# quantum-switch-control-panel.net
KiCad netlist of a schematic drawn in Altium Designer
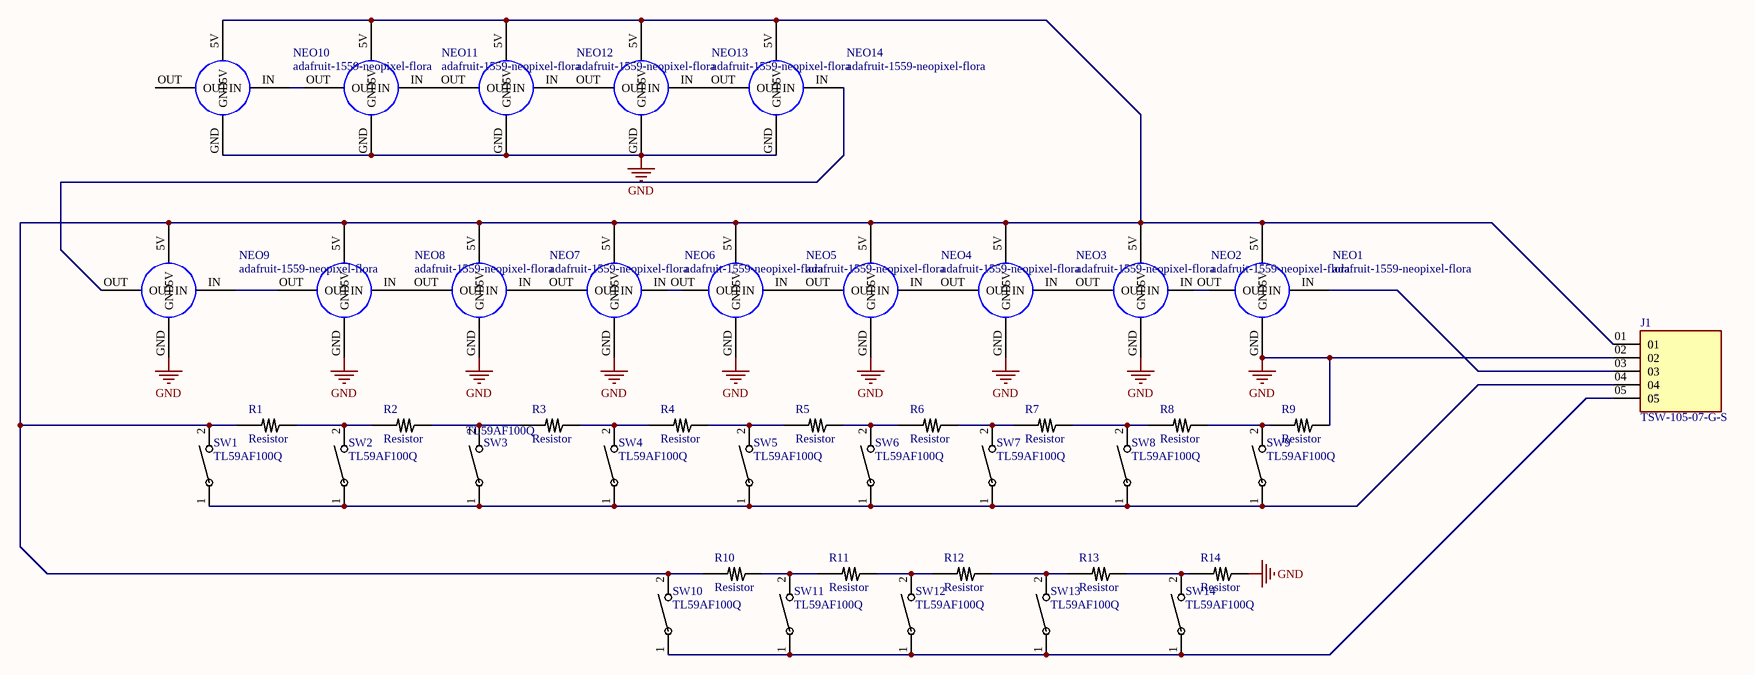
[diagram p0: quantum-switch-control-panel.SchDoc]

(export (version "E")
  (design (tool "Eeschema 10.0.6"))
  (components
    (comp (ref "J1")
      (value "TSW-105-07-G-S")
      (footprint "SAMTEC_TSW-105-07-G-S")
      (fields (field (name "MF") "Samtec Inc."))
      (libsource (lib "SchlibLafe") (part "TSW-105-07-G-S"))
    )
    (comp (ref "NEO1")
      (value "adafruit-1559-neopixel-flora")
      (footprint "adafruit-1559-neopixel-flora")
      (libsource (lib "SchlibLafe") (part "adafruit-1559-neopixel-flora"))
    )
    (comp (ref "NEO2")
      (value "adafruit-1559-neopixel-flora")
      (footprint "adafruit-1559-neopixel-flora")
      (libsource (lib "SchlibLafe") (part "adafruit-1559-neopixel-flora"))
    )
    (comp (ref "NEO3")
      (value "adafruit-1559-neopixel-flora")
      (footprint "adafruit-1559-neopixel-flora")
      (libsource (lib "SchlibLafe") (part "adafruit-1559-neopixel-flora"))
    )
    (comp (ref "NEO4")
      (value "adafruit-1559-neopixel-flora")
      (footprint "adafruit-1559-neopixel-flora")
      (libsource (lib "SchlibLafe") (part "adafruit-1559-neopixel-flora"))
    )
    (comp (ref "NEO5")
      (value "adafruit-1559-neopixel-flora")
      (footprint "adafruit-1559-neopixel-flora")
      (libsource (lib "SchlibLafe") (part "adafruit-1559-neopixel-flora"))
    )
    (comp (ref "NEO6")
      (value "adafruit-1559-neopixel-flora")
      (footprint "adafruit-1559-neopixel-flora")
      (libsource (lib "SchlibLafe") (part "adafruit-1559-neopixel-flora"))
    )
    (comp (ref "NEO7")
      (value "adafruit-1559-neopixel-flora")
      (footprint "adafruit-1559-neopixel-flora")
      (libsource (lib "SchlibLafe") (part "adafruit-1559-neopixel-flora"))
    )
    (comp (ref "NEO8")
      (value "adafruit-1559-neopixel-flora")
      (footprint "adafruit-1559-neopixel-flora")
      (libsource (lib "SchlibLafe") (part "adafruit-1559-neopixel-flora"))
    )
    (comp (ref "NEO9")
      (value "adafruit-1559-neopixel-flora")
      (footprint "adafruit-1559-neopixel-flora")
      (libsource (lib "SchlibLafe") (part "adafruit-1559-neopixel-flora"))
    )
    (comp (ref "NEO10")
      (value "adafruit-1559-neopixel-flora")
      (footprint "adafruit-1559-neopixel-flora")
      (libsource (lib "SchlibLafe") (part "adafruit-1559-neopixel-flora"))
    )
    (comp (ref "NEO11")
      (value "adafruit-1559-neopixel-flora")
      (footprint "adafruit-1559-neopixel-flora")
      (libsource (lib "SchlibLafe") (part "adafruit-1559-neopixel-flora"))
    )
    (comp (ref "NEO12")
      (value "adafruit-1559-neopixel-flora")
      (footprint "adafruit-1559-neopixel-flora")
      (libsource (lib "SchlibLafe") (part "adafruit-1559-neopixel-flora"))
    )
    (comp (ref "NEO13")
      (value "adafruit-1559-neopixel-flora")
      (footprint "adafruit-1559-neopixel-flora")
      (libsource (lib "SchlibLafe") (part "adafruit-1559-neopixel-flora"))
    )
    (comp (ref "NEO14")
      (value "adafruit-1559-neopixel-flora")
      (footprint "adafruit-1559-neopixel-flora")
      (libsource (lib "SchlibLafe") (part "adafruit-1559-neopixel-flora"))
    )
    (comp (ref "R1")
      (value "Resistor")
      (footprint "thruhole resistor")
      (libsource (lib "SchlibLafe") (part "Resistor"))
    )
    (comp (ref "R2")
      (value "Resistor")
      (footprint "thruhole resistor")
      (libsource (lib "SchlibLafe") (part "Resistor"))
    )
    (comp (ref "R3")
      (value "Resistor")
      (footprint "thruhole resistor")
      (libsource (lib "SchlibLafe") (part "Resistor"))
    )
    (comp (ref "R4")
      (value "Resistor")
      (footprint "thruhole resistor")
      (libsource (lib "SchlibLafe") (part "Resistor"))
    )
    (comp (ref "R5")
      (value "Resistor")
      (footprint "thruhole resistor")
      (libsource (lib "SchlibLafe") (part "Resistor"))
    )
    (comp (ref "R6")
      (value "Resistor")
      (footprint "thruhole resistor")
      (libsource (lib "SchlibLafe") (part "Resistor"))
    )
    (comp (ref "R7")
      (value "Resistor")
      (footprint "thruhole resistor")
      (libsource (lib "SchlibLafe") (part "Resistor"))
    )
    (comp (ref "R8")
      (value "Resistor")
      (footprint "thruhole resistor")
      (libsource (lib "SchlibLafe") (part "Resistor"))
    )
    (comp (ref "R9")
      (value "Resistor")
      (footprint "thruhole resistor")
      (libsource (lib "SchlibLafe") (part "Resistor"))
    )
    (comp (ref "R10")
      (value "Resistor")
      (footprint "thruhole resistor")
      (libsource (lib "SchlibLafe") (part "Resistor"))
    )
    (comp (ref "R11")
      (value "Resistor")
      (footprint "thruhole resistor")
      (libsource (lib "SchlibLafe") (part "Resistor"))
    )
    (comp (ref "R12")
      (value "Resistor")
      (footprint "thruhole resistor")
      (libsource (lib "SchlibLafe") (part "Resistor"))
    )
    (comp (ref "R13")
      (value "Resistor")
      (footprint "thruhole resistor")
      (libsource (lib "SchlibLafe") (part "Resistor"))
    )
    (comp (ref "R14")
      (value "Resistor")
      (footprint "thruhole resistor")
      (libsource (lib "SchlibLafe") (part "Resistor"))
    )
    (comp (ref "SW1")
      (value "TL59AF100Q")
      (footprint "SW_TL59AF100Q_EWI")
      (description "No Description Available")
      (fields (field (name "COPYRIGHT") "Copyright (C) 2024 Ultra Librarian. All rights reserved."))
      (libsource (lib "SchlibLafe") (part "TL59AF100Q"))
    )
    (comp (ref "SW2")
      (value "TL59AF100Q")
      (footprint "SW_TL59AF100Q_EWI")
      (description "No Description Available")
      (fields (field (name "COPYRIGHT") "Copyright (C) 2024 Ultra Librarian. All rights reserved."))
      (libsource (lib "SchlibLafe") (part "TL59AF100Q"))
    )
    (comp (ref "SW3")
      (value "TL59AF100Q")
      (footprint "SW_TL59AF100Q_EWI")
      (description "No Description Available")
      (fields (field (name "COPYRIGHT") "Copyright (C) 2024 Ultra Librarian. All rights reserved."))
      (libsource (lib "SchlibLafe") (part "TL59AF100Q"))
    )
    (comp (ref "SW4")
      (value "TL59AF100Q")
      (footprint "SW_TL59AF100Q_EWI")
      (description "No Description Available")
      (fields (field (name "COPYRIGHT") "Copyright (C) 2024 Ultra Librarian. All rights reserved."))
      (libsource (lib "SchlibLafe") (part "TL59AF100Q"))
    )
    (comp (ref "SW5")
      (value "TL59AF100Q")
      (footprint "SW_TL59AF100Q_EWI")
      (description "No Description Available")
      (fields (field (name "COPYRIGHT") "Copyright (C) 2024 Ultra Librarian. All rights reserved."))
      (libsource (lib "SchlibLafe") (part "TL59AF100Q"))
    )
    (comp (ref "SW6")
      (value "TL59AF100Q")
      (footprint "SW_TL59AF100Q_EWI")
      (description "No Description Available")
      (fields (field (name "COPYRIGHT") "Copyright (C) 2024 Ultra Librarian. All rights reserved."))
      (libsource (lib "SchlibLafe") (part "TL59AF100Q"))
    )
    (comp (ref "SW7")
      (value "TL59AF100Q")
      (footprint "SW_TL59AF100Q_EWI")
      (description "No Description Available")
      (fields (field (name "COPYRIGHT") "Copyright (C) 2024 Ultra Librarian. All rights reserved."))
      (libsource (lib "SchlibLafe") (part "TL59AF100Q"))
    )
    (comp (ref "SW8")
      (value "TL59AF100Q")
      (footprint "SW_TL59AF100Q_EWI")
      (description "No Description Available")
      (fields (field (name "COPYRIGHT") "Copyright (C) 2024 Ultra Librarian. All rights reserved."))
      (libsource (lib "SchlibLafe") (part "TL59AF100Q"))
    )
    (comp (ref "SW9")
      (value "TL59AF100Q")
      (footprint "SW_TL59AF100Q_EWI")
      (description "No Description Available")
      (fields (field (name "COPYRIGHT") "Copyright (C) 2024 Ultra Librarian. All rights reserved."))
      (libsource (lib "SchlibLafe") (part "TL59AF100Q"))
    )
    (comp (ref "SW10")
      (value "TL59AF100Q")
      (footprint "SW_TL59AF100Q_EWI")
      (description "No Description Available")
      (fields (field (name "COPYRIGHT") "Copyright (C) 2024 Ultra Librarian. All rights reserved."))
      (libsource (lib "SchlibLafe") (part "TL59AF100Q"))
    )
    (comp (ref "SW11")
      (value "TL59AF100Q")
      (footprint "SW_TL59AF100Q_EWI")
      (description "No Description Available")
      (fields (field (name "COPYRIGHT") "Copyright (C) 2024 Ultra Librarian. All rights reserved."))
      (libsource (lib "SchlibLafe") (part "TL59AF100Q"))
    )
    (comp (ref "SW12")
      (value "TL59AF100Q")
      (footprint "SW_TL59AF100Q_EWI")
      (description "No Description Available")
      (fields (field (name "COPYRIGHT") "Copyright (C) 2024 Ultra Librarian. All rights reserved."))
      (libsource (lib "SchlibLafe") (part "TL59AF100Q"))
    )
    (comp (ref "SW13")
      (value "TL59AF100Q")
      (footprint "SW_TL59AF100Q_EWI")
      (description "No Description Available")
      (fields (field (name "COPYRIGHT") "Copyright (C) 2024 Ultra Librarian. All rights reserved."))
      (libsource (lib "SchlibLafe") (part "TL59AF100Q"))
    )
    (comp (ref "SW14")
      (value "TL59AF100Q")
      (footprint "SW_TL59AF100Q_EWI")
      (description "No Description Available")
      (fields (field (name "COPYRIGHT") "Copyright (C) 2024 Ultra Librarian. All rights reserved."))
      (libsource (lib "SchlibLafe") (part "TL59AF100Q"))
    )
  )
  (nets
    (net (code "1") (name "GND") (class "Default")
      (node (ref "J1") (pin "02") (pinfunction "02_02") (pintype "passive"))
      (node (ref "NEO1") (pin "GND") (pinfunction "GND_GND") (pintype "passive"))
      (node (ref "NEO10") (pin "GND") (pinfunction "GND_GND") (pintype "passive"))
      (node (ref "NEO11") (pin "GND") (pinfunction "GND_GND") (pintype "passive"))
      (node (ref "NEO12") (pin "GND") (pinfunction "GND_GND") (pintype "passive"))
      (node (ref "NEO13") (pin "GND") (pinfunction "GND_GND") (pintype "passive"))
      (node (ref "NEO14") (pin "GND") (pinfunction "GND_GND") (pintype "passive"))
      (node (ref "NEO2") (pin "GND") (pinfunction "GND_GND") (pintype "passive"))
      (node (ref "NEO3") (pin "GND") (pinfunction "GND_GND") (pintype "passive"))
      (node (ref "NEO4") (pin "GND") (pinfunction "GND_GND") (pintype "passive"))
      (node (ref "NEO5") (pin "GND") (pinfunction "GND_GND") (pintype "passive"))
      (node (ref "NEO6") (pin "GND") (pinfunction "GND_GND") (pintype "passive"))
      (node (ref "NEO7") (pin "GND") (pinfunction "GND_GND") (pintype "passive"))
      (node (ref "NEO8") (pin "GND") (pinfunction "GND_GND") (pintype "passive"))
      (node (ref "NEO9") (pin "GND") (pinfunction "GND_GND") (pintype "passive"))
      (node (ref "R14") (pin "1") (pinfunction "1_1") (pintype "passive"))
      (node (ref "R9") (pin "1") (pinfunction "1_1") (pintype "passive"))
    )
    (net (code "2") (name "Net-(J1-Pad01)") (class "Default")
      (node (ref "J1") (pin "01") (pinfunction "01_01") (pintype "passive"))
      (node (ref "NEO1") (pin "5V") (pinfunction "5V_5V") (pintype "passive"))
      (node (ref "NEO10") (pin "5V") (pinfunction "5V_5V") (pintype "passive"))
      (node (ref "NEO11") (pin "5V") (pinfunction "5V_5V") (pintype "passive"))
      (node (ref "NEO12") (pin "5V") (pinfunction "5V_5V") (pintype "passive"))
      (node (ref "NEO13") (pin "5V") (pinfunction "5V_5V") (pintype "passive"))
      (node (ref "NEO14") (pin "5V") (pinfunction "5V_5V") (pintype "passive"))
      (node (ref "NEO2") (pin "5V") (pinfunction "5V_5V") (pintype "passive"))
      (node (ref "NEO3") (pin "5V") (pinfunction "5V_5V") (pintype "passive"))
      (node (ref "NEO4") (pin "5V") (pinfunction "5V_5V") (pintype "passive"))
      (node (ref "NEO5") (pin "5V") (pinfunction "5V_5V") (pintype "passive"))
      (node (ref "NEO6") (pin "5V") (pinfunction "5V_5V") (pintype "passive"))
      (node (ref "NEO7") (pin "5V") (pinfunction "5V_5V") (pintype "passive"))
      (node (ref "NEO8") (pin "5V") (pinfunction "5V_5V") (pintype "passive"))
      (node (ref "NEO9") (pin "5V") (pinfunction "5V_5V") (pintype "passive"))
      (node (ref "R1") (pin "2") (pinfunction "2_2") (pintype "passive"))
      (node (ref "R10") (pin "2") (pinfunction "2_2") (pintype "passive"))
      (node (ref "SW1") (pin "2") (pinfunction "2_2") (pintype "passive"))
      (node (ref "SW10") (pin "2") (pinfunction "2_2") (pintype "passive"))
    )
    (net (code "3") (name "Net-(J1-Pad03)") (class "Default")
      (node (ref "J1") (pin "03") (pinfunction "03_03") (pintype "passive"))
      (node (ref "NEO1") (pin "IN") (pinfunction "IN_IN") (pintype "passive"))
    )
    (net (code "4") (name "Net-(J1-Pad04)") (class "Default")
      (node (ref "J1") (pin "04") (pinfunction "04_04") (pintype "passive"))
      (node (ref "SW1") (pin "1") (pinfunction "1_1") (pintype "passive"))
      (node (ref "SW2") (pin "1") (pinfunction "1_1") (pintype "passive"))
      (node (ref "SW3") (pin "1") (pinfunction "1_1") (pintype "passive"))
      (node (ref "SW4") (pin "1") (pinfunction "1_1") (pintype "passive"))
      (node (ref "SW5") (pin "1") (pinfunction "1_1") (pintype "passive"))
      (node (ref "SW6") (pin "1") (pinfunction "1_1") (pintype "passive"))
      (node (ref "SW7") (pin "1") (pinfunction "1_1") (pintype "passive"))
      (node (ref "SW8") (pin "1") (pinfunction "1_1") (pintype "passive"))
      (node (ref "SW9") (pin "1") (pinfunction "1_1") (pintype "passive"))
    )
    (net (code "5") (name "Net-(J1-Pad05)") (class "Default")
      (node (ref "J1") (pin "05") (pinfunction "05_05") (pintype "passive"))
      (node (ref "SW10") (pin "1") (pinfunction "1_1") (pintype "passive"))
      (node (ref "SW11") (pin "1") (pinfunction "1_1") (pintype "passive"))
      (node (ref "SW12") (pin "1") (pinfunction "1_1") (pintype "passive"))
      (node (ref "SW13") (pin "1") (pinfunction "1_1") (pintype "passive"))
      (node (ref "SW14") (pin "1") (pinfunction "1_1") (pintype "passive"))
    )
    (net (code "6") (name "Net-(NEO1-PadOUT)") (class "Default")
      (node (ref "NEO1") (pin "OUT") (pinfunction "OUT_OUT") (pintype "passive"))
      (node (ref "NEO2") (pin "IN") (pinfunction "IN_IN") (pintype "passive"))
    )
    (net (code "7") (name "Net-(NEO2-PadOUT)") (class "Default")
      (node (ref "NEO2") (pin "OUT") (pinfunction "OUT_OUT") (pintype "passive"))
      (node (ref "NEO3") (pin "IN") (pinfunction "IN_IN") (pintype "passive"))
    )
    (net (code "8") (name "Net-(NEO3-PadOUT)") (class "Default")
      (node (ref "NEO3") (pin "OUT") (pinfunction "OUT_OUT") (pintype "passive"))
      (node (ref "NEO4") (pin "IN") (pinfunction "IN_IN") (pintype "passive"))
    )
    (net (code "9") (name "Net-(NEO4-PadOUT)") (class "Default")
      (node (ref "NEO4") (pin "OUT") (pinfunction "OUT_OUT") (pintype "passive"))
      (node (ref "NEO5") (pin "IN") (pinfunction "IN_IN") (pintype "passive"))
    )
    (net (code "10") (name "Net-(NEO5-PadOUT)") (class "Default")
      (node (ref "NEO5") (pin "OUT") (pinfunction "OUT_OUT") (pintype "passive"))
      (node (ref "NEO6") (pin "IN") (pinfunction "IN_IN") (pintype "passive"))
    )
    (net (code "11") (name "Net-(NEO6-PadOUT)") (class "Default")
      (node (ref "NEO6") (pin "OUT") (pinfunction "OUT_OUT") (pintype "passive"))
      (node (ref "NEO7") (pin "IN") (pinfunction "IN_IN") (pintype "passive"))
    )
    (net (code "12") (name "Net-(NEO7-PadOUT)") (class "Default")
      (node (ref "NEO7") (pin "OUT") (pinfunction "OUT_OUT") (pintype "passive"))
      (node (ref "NEO8") (pin "IN") (pinfunction "IN_IN") (pintype "passive"))
    )
    (net (code "13") (name "Net-(NEO8-PadOUT)") (class "Default")
      (node (ref "NEO8") (pin "OUT") (pinfunction "OUT_OUT") (pintype "passive"))
      (node (ref "NEO9") (pin "IN") (pinfunction "IN_IN") (pintype "passive"))
    )
    (net (code "14") (name "Net-(NEO10-PadIN)") (class "Default")
      (node (ref "NEO10") (pin "IN") (pinfunction "IN_IN") (pintype "passive"))
      (node (ref "NEO11") (pin "OUT") (pinfunction "OUT_OUT") (pintype "passive"))
    )
    (net (code "15") (name "Net-(NEO11-PadIN)") (class "Default")
      (node (ref "NEO11") (pin "IN") (pinfunction "IN_IN") (pintype "passive"))
      (node (ref "NEO12") (pin "OUT") (pinfunction "OUT_OUT") (pintype "passive"))
    )
    (net (code "16") (name "Net-(NEO12-PadIN)") (class "Default")
      (node (ref "NEO12") (pin "IN") (pinfunction "IN_IN") (pintype "passive"))
      (node (ref "NEO13") (pin "OUT") (pinfunction "OUT_OUT") (pintype "passive"))
    )
    (net (code "17") (name "Net-(NEO13-PadIN)") (class "Default")
      (node (ref "NEO13") (pin "IN") (pinfunction "IN_IN") (pintype "passive"))
      (node (ref "NEO14") (pin "OUT") (pinfunction "OUT_OUT") (pintype "passive"))
    )
    (net (code "18") (name "Net-(NEO14-PadIN)") (class "Default")
      (node (ref "NEO14") (pin "IN") (pinfunction "IN_IN") (pintype "passive"))
      (node (ref "NEO9") (pin "OUT") (pinfunction "OUT_OUT") (pintype "passive"))
    )
    (net (code "19") (name "Net-(R1-Pad1)") (class "Default")
      (node (ref "R1") (pin "1") (pinfunction "1_1") (pintype "passive"))
      (node (ref "R2") (pin "2") (pinfunction "2_2") (pintype "passive"))
      (node (ref "SW2") (pin "2") (pinfunction "2_2") (pintype "passive"))
    )
    (net (code "20") (name "Net-(R2-Pad1)") (class "Default")
      (node (ref "R2") (pin "1") (pinfunction "1_1") (pintype "passive"))
      (node (ref "R3") (pin "2") (pinfunction "2_2") (pintype "passive"))
      (node (ref "SW3") (pin "2") (pinfunction "2_2") (pintype "passive"))
    )
    (net (code "21") (name "Net-(R3-Pad1)") (class "Default")
      (node (ref "R3") (pin "1") (pinfunction "1_1") (pintype "passive"))
      (node (ref "R4") (pin "2") (pinfunction "2_2") (pintype "passive"))
      (node (ref "SW4") (pin "2") (pinfunction "2_2") (pintype "passive"))
    )
    (net (code "22") (name "Net-(R4-Pad1)") (class "Default")
      (node (ref "R4") (pin "1") (pinfunction "1_1") (pintype "passive"))
      (node (ref "R5") (pin "2") (pinfunction "2_2") (pintype "passive"))
      (node (ref "SW5") (pin "2") (pinfunction "2_2") (pintype "passive"))
    )
    (net (code "23") (name "Net-(R5-Pad1)") (class "Default")
      (node (ref "R5") (pin "1") (pinfunction "1_1") (pintype "passive"))
      (node (ref "R6") (pin "2") (pinfunction "2_2") (pintype "passive"))
      (node (ref "SW6") (pin "2") (pinfunction "2_2") (pintype "passive"))
    )
    (net (code "24") (name "Net-(R6-Pad1)") (class "Default")
      (node (ref "R6") (pin "1") (pinfunction "1_1") (pintype "passive"))
      (node (ref "R7") (pin "2") (pinfunction "2_2") (pintype "passive"))
      (node (ref "SW7") (pin "2") (pinfunction "2_2") (pintype "passive"))
    )
    (net (code "25") (name "Net-(R7-Pad1)") (class "Default")
      (node (ref "R7") (pin "1") (pinfunction "1_1") (pintype "passive"))
      (node (ref "R8") (pin "2") (pinfunction "2_2") (pintype "passive"))
      (node (ref "SW8") (pin "2") (pinfunction "2_2") (pintype "passive"))
    )
    (net (code "26") (name "Net-(R8-Pad1)") (class "Default")
      (node (ref "R8") (pin "1") (pinfunction "1_1") (pintype "passive"))
      (node (ref "R9") (pin "2") (pinfunction "2_2") (pintype "passive"))
      (node (ref "SW9") (pin "2") (pinfunction "2_2") (pintype "passive"))
    )
    (net (code "27") (name "Net-(R10-Pad1)") (class "Default")
      (node (ref "R10") (pin "1") (pinfunction "1_1") (pintype "passive"))
      (node (ref "R11") (pin "2") (pinfunction "2_2") (pintype "passive"))
      (node (ref "SW11") (pin "2") (pinfunction "2_2") (pintype "passive"))
    )
    (net (code "28") (name "Net-(R11-Pad1)") (class "Default")
      (node (ref "R11") (pin "1") (pinfunction "1_1") (pintype "passive"))
      (node (ref "R12") (pin "2") (pinfunction "2_2") (pintype "passive"))
      (node (ref "SW12") (pin "2") (pinfunction "2_2") (pintype "passive"))
    )
    (net (code "29") (name "Net-(R12-Pad1)") (class "Default")
      (node (ref "R12") (pin "1") (pinfunction "1_1") (pintype "passive"))
      (node (ref "R13") (pin "2") (pinfunction "2_2") (pintype "passive"))
      (node (ref "SW13") (pin "2") (pinfunction "2_2") (pintype "passive"))
    )
    (net (code "30") (name "Net-(R13-Pad1)") (class "Default")
      (node (ref "R13") (pin "1") (pinfunction "1_1") (pintype "passive"))
      (node (ref "R14") (pin "2") (pinfunction "2_2") (pintype "passive"))
      (node (ref "SW14") (pin "2") (pinfunction "2_2") (pintype "passive"))
    )
    (net (code "31") (name "unconnected-(NEO10-PadOUT)") (class "Default")
      (node (ref "NEO10") (pin "OUT") (pinfunction "OUT_OUT") (pintype "passive"))
    )
  )
)
